# Power.net
KiCad netlist of a schematic drawn in Altium Designer
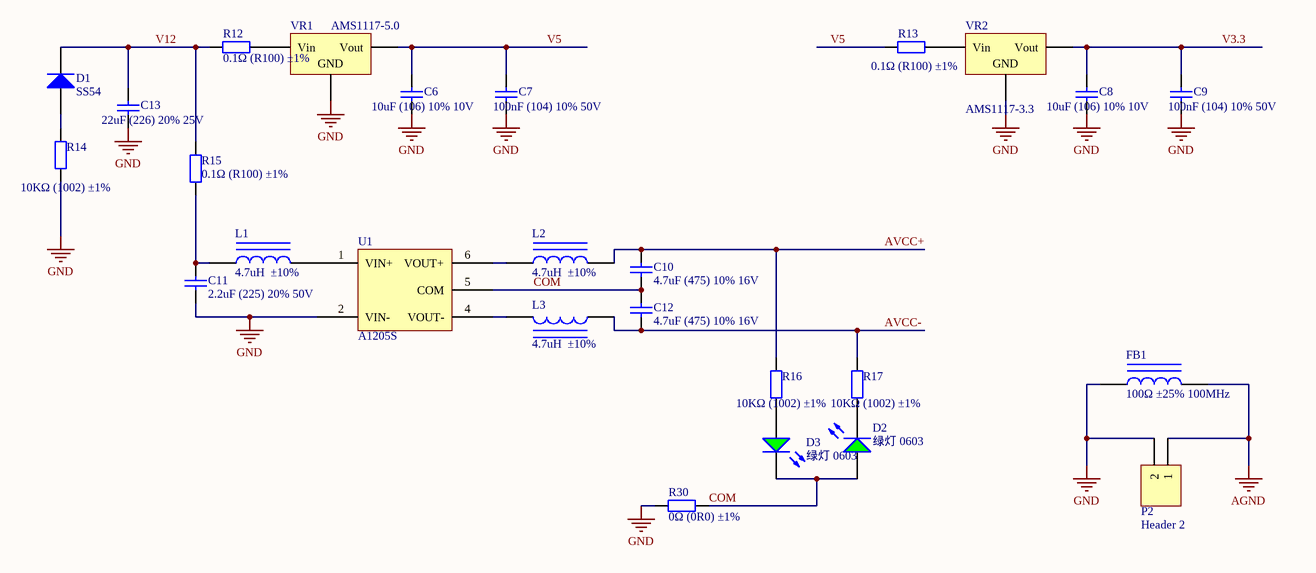
[diagram p0: Power.SchDoc]

(export (version "E")
  (design (tool "Eeschema 10.0.6"))
  (components
    (comp (ref "C6")
      (value "10uF (106) 10% 10V")
      (footprint "0603_C")
      (description "贴片电容")
      (libsource (lib "Miscellaneous Devices LC") (part "0603 10uF (106) 10% 10V"))
    )
    (comp (ref "C7")
      (value "100nF (104) 10% 50V")
      (footprint "0603_C")
      (description "贴片电容")
      (libsource (lib "Miscellaneous Devices LC") (part "0603 100nF (104) 10% 50V"))
    )
    (comp (ref "C8")
      (value "10uF (106) 10% 10V")
      (footprint "0603_C")
      (description "贴片电容")
      (libsource (lib "Miscellaneous Devices LC") (part "0603 10uF (106) 10% 10V"))
    )
    (comp (ref "C9")
      (value "100nF (104) 10% 50V")
      (footprint "0603_C")
      (description "贴片电容")
      (libsource (lib "Miscellaneous Devices LC") (part "0603 100nF (104) 10% 50V"))
    )
    (comp (ref "C10")
      (value "4.7uF (475) 10% 16V")
      (footprint "0603_C")
      (description "贴片电容")
      (libsource (lib "Miscellaneous Devices LC") (part "0603 4.7uF (475) 10% 16V"))
    )
    (comp (ref "C11")
      (value "2.2uF (225) 20% 50V")
      (footprint "0805_C")
      (description "贴片电容")
      (libsource (lib "Miscellaneous Devices LC") (part "0805 2.2uF (225) 20% 50V"))
    )
    (comp (ref "C12")
      (value "4.7uF (475) 10% 16V")
      (footprint "0603_C")
      (description "贴片电容")
      (libsource (lib "Miscellaneous Devices LC") (part "0603 4.7uF (475) 10% 16V"))
    )
    (comp (ref "C13")
      (value "22uF (226) 20% 25V")
      (footprint "0805_C")
      (description "贴片电容")
      (libsource (lib "Miscellaneous Devices LC") (part "0805 22uF (226) 20% 25V"))
    )
    (comp (ref "D1")
      (value "SS54")
      (footprint "SMA(DO-214AC)_S1")
      (description "二极管")
      (libsource (lib "Miscellaneous Devices LC") (part "SMA(DO-214AC) SS54"))
    )
    (comp (ref "D2")
      (value "绿灯 0603")
      (footprint "0603_LED_S1")
      (description "发光二极管")
      (libsource (lib "Miscellaneous Devices LC") (part "0603 绿灯"))
    )
    (comp (ref "D3")
      (value "绿灯 0603")
      (footprint "0603_LED_S1")
      (description "发光二极管")
      (libsource (lib "Miscellaneous Devices LC") (part "0603 绿灯"))
    )
    (comp (ref "FB1")
      (value "100Ω ±25% 100MHz")
      (footprint "0805_L")
      (description "贴片磁珠")
      (libsource (lib "Miscellaneous Devices LC") (part "0805 100Ω 25% 100MHz"))
    )
    (comp (ref "L1")
      (value "4.7uH  ±10%")
      (footprint "1206_L")
      (description "贴片电感")
      (libsource (lib "") (part "1206 4.7uH  10%_1"))
    )
    (comp (ref "L2")
      (value "4.7uH  ±10%")
      (footprint "1206_L")
      (description "贴片电感")
      (libsource (lib "") (part "1206 4.7uH  10%_1"))
    )
    (comp (ref "L3")
      (value "4.7uH  ±10%")
      (footprint "1206_L")
      (description "贴片电感")
      (libsource (lib "Miscellaneous Devices LC") (part "1206 4.7uH  10%"))
    )
    (comp (ref "P2")
      (value "Header 2")
      (footprint "HDR1X2")
      (description "Header, 2-Pin")
      (fields (field (name "PUBLISHER") "Altium Limited"))
      (libsource (lib "Miscellaneous Connectors") (part "Header 2"))
    )
    (comp (ref "R12")
      (value "0.1Ω (R100) ±1%")
      (footprint "1206_R")
      (description "贴片电阻")
      (libsource (lib "Miscellaneous Devices LC") (part "1206 0.1Ω (R100) 1%"))
    )
    (comp (ref "R13")
      (value "0.1Ω (R100) ±1%")
      (footprint "1206_R")
      (description "贴片电阻")
      (libsource (lib "Miscellaneous Devices LC") (part "1206 0.1Ω (R100) 1%"))
    )
    (comp (ref "R14")
      (value "10KΩ (1002) ±1%")
      (footprint "0805_R")
      (description "贴片电阻")
      (libsource (lib "Miscellaneous Devices LC") (part "0805 10KΩ (1002) 1%"))
    )
    (comp (ref "R15")
      (value "0.1Ω (R100) ±1%")
      (footprint "1206_R")
      (description "贴片电阻")
      (libsource (lib "") (part "1206 0.1Ω (R100) 1%_1"))
    )
    (comp (ref "R16")
      (value "10KΩ (1002) ±1%")
      (footprint "0603_R")
      (description "贴片电阻")
      (libsource (lib "Miscellaneous Devices LC") (part "0603 10KΩ (1002) 1%"))
    )
    (comp (ref "R17")
      (value "10KΩ (1002) ±1%")
      (footprint "0603_R")
      (description "贴片电阻")
      (libsource (lib "Miscellaneous Devices LC") (part "0603 10KΩ (1002) 1%"))
    )
    (comp (ref "R30")
      (value "0Ω (0R0) ±1%")
      (footprint "1206_R")
      (description "贴片电阻")
      (libsource (lib "Miscellaneous Devices LC") (part "1206 0Ω (0R0) 1%"))
    )
    (comp (ref "U1") (value "A1205S") (footprint "A1205S") (libsource (lib "CHK-I") (part "A1205S")))
    (comp (ref "VR1")
      (value "AMS1117-5.0")
      (footprint "SOT-223")
      (description "低压差线性稳压(LDO)")
      (libsource (lib "Miscellaneous Devices LC") (part "SOT-223 AMS1117-5.0"))
    )
    (comp (ref "VR2")
      (value "AMS1117-3.3")
      (footprint "SOT-223")
      (description "低压差线性稳压(LDO)")
      (libsource (lib "Miscellaneous Devices LC") (part "SOT-223 AMS1117-3.3"))
    )
  )
  (nets
    (net (code "1") (name "/AVCC+") (class "Default")
      (node (ref "C10") (pin "2") (pinfunction "2_2") (pintype "passive"))
      (node (ref "L2") (pin "2") (pinfunction "2_2") (pintype "passive"))
      (node (ref "R16") (pin "2") (pinfunction "2_2") (pintype "passive"))
    )
    (net (code "2") (name "/AVCC-") (class "Default")
      (node (ref "C12") (pin "1") (pinfunction "1_1") (pintype "passive"))
      (node (ref "L3") (pin "2") (pinfunction "2_2") (pintype "passive"))
      (node (ref "R17") (pin "2") (pinfunction "2_2") (pintype "passive"))
    )
    (net (code "3") (name "/COM") (class "Default")
      (node (ref "C10") (pin "1") (pinfunction "1_1") (pintype "passive"))
      (node (ref "C12") (pin "2") (pinfunction "2_2") (pintype "passive"))
      (node (ref "D2") (pin "A") (pinfunction "A_A") (pintype "passive"))
      (node (ref "D3") (pin "K") (pinfunction "K_K") (pintype "passive"))
      (node (ref "R30") (pin "2") (pinfunction "2_2") (pintype "passive"))
      (node (ref "U1") (pin "5") (pinfunction "COM_5") (pintype "passive"))
    )
    (net (code "4") (name "/V3.3") (class "Default")
      (node (ref "C8") (pin "2") (pinfunction "2_2") (pintype "passive"))
      (node (ref "C9") (pin "2") (pinfunction "2_2") (pintype "passive"))
      (node (ref "VR2") (pin "2") (pinfunction "Vout_2") (pintype "passive"))
    )
    (net (code "5") (name "/V5") (class "Default")
      (node (ref "C6") (pin "2") (pinfunction "2_2") (pintype "passive"))
      (node (ref "C7") (pin "2") (pinfunction "2_2") (pintype "passive"))
      (node (ref "R13") (pin "1") (pinfunction "1_1") (pintype "passive"))
      (node (ref "VR1") (pin "2") (pinfunction "Vout_2") (pintype "passive"))
    )
    (net (code "6") (name "/V12") (class "Default")
      (node (ref "C13") (pin "2") (pinfunction "2_2") (pintype "passive"))
      (node (ref "D1") (pin "2") (pinfunction "K_2") (pintype "passive"))
      (node (ref "R12") (pin "1") (pinfunction "1_1") (pintype "passive"))
      (node (ref "R15") (pin "2") (pinfunction "2_2") (pintype "passive"))
    )
    (net (code "7") (name "AGND") (class "Default")
      (node (ref "FB1") (pin "2") (pinfunction "2_2") (pintype "passive"))
      (node (ref "P2") (pin "1") (pinfunction "1_1") (pintype "passive"))
    )
    (net (code "8") (name "GND") (class "Default")
      (node (ref "C11") (pin "1") (pinfunction "1_1") (pintype "passive"))
      (node (ref "C13") (pin "1") (pinfunction "1_1") (pintype "passive"))
      (node (ref "C6") (pin "1") (pinfunction "1_1") (pintype "passive"))
      (node (ref "C7") (pin "1") (pinfunction "1_1") (pintype "passive"))
      (node (ref "C8") (pin "1") (pinfunction "1_1") (pintype "passive"))
      (node (ref "C9") (pin "1") (pinfunction "1_1") (pintype "passive"))
      (node (ref "FB1") (pin "1") (pinfunction "1_1") (pintype "passive"))
      (node (ref "P2") (pin "2") (pinfunction "2_2") (pintype "passive"))
      (node (ref "R14") (pin "1") (pinfunction "1_1") (pintype "passive"))
      (node (ref "R30") (pin "1") (pinfunction "1_1") (pintype "passive"))
      (node (ref "U1") (pin "2") (pinfunction "VIN-_2") (pintype "passive"))
      (node (ref "VR1") (pin "1") (pinfunction "GND_1") (pintype "passive"))
      (node (ref "VR2") (pin "1") (pinfunction "GND_1") (pintype "passive"))
    )
    (net (code "9") (name "Net-(C11-Pad2)") (class "Default")
      (node (ref "C11") (pin "2") (pinfunction "2_2") (pintype "passive"))
      (node (ref "L1") (pin "1") (pinfunction "1_1") (pintype "passive"))
      (node (ref "R15") (pin "1") (pinfunction "1_1") (pintype "passive"))
    )
    (net (code "10") (name "Net-(D1-A)") (class "Default")
      (node (ref "D1") (pin "1") (pinfunction "A_1") (pintype "passive"))
      (node (ref "R14") (pin "2") (pinfunction "2_2") (pintype "passive"))
    )
    (net (code "11") (name "Net-(D2-PadK)") (class "Default")
      (node (ref "D2") (pin "K") (pinfunction "K_K") (pintype "passive"))
      (node (ref "R17") (pin "1") (pinfunction "1_1") (pintype "passive"))
    )
    (net (code "12") (name "Net-(D3-PadA)") (class "Default")
      (node (ref "D3") (pin "A") (pinfunction "A_A") (pintype "passive"))
      (node (ref "R16") (pin "1") (pinfunction "1_1") (pintype "passive"))
    )
    (net (code "13") (name "Net-(U1-VIN+)") (class "Default")
      (node (ref "L1") (pin "2") (pinfunction "2_2") (pintype "passive"))
      (node (ref "U1") (pin "1") (pinfunction "VIN+_1") (pintype "passive"))
    )
    (net (code "14") (name "Net-(U1-VOUT+)") (class "Default")
      (node (ref "L2") (pin "1") (pinfunction "1_1") (pintype "passive"))
      (node (ref "U1") (pin "6") (pinfunction "VOUT+_6") (pintype "passive"))
    )
    (net (code "15") (name "Net-(U1-VOUT-)") (class "Default")
      (node (ref "L3") (pin "1") (pinfunction "1_1") (pintype "passive"))
      (node (ref "U1") (pin "4") (pinfunction "VOUT-_4") (pintype "passive"))
    )
    (net (code "16") (name "Net-(VR1-Vin)") (class "Default")
      (node (ref "R12") (pin "2") (pinfunction "2_2") (pintype "passive"))
      (node (ref "VR1") (pin "3") (pinfunction "Vin_3") (pintype "passive"))
    )
    (net (code "17") (name "Net-(VR2-Vin)") (class "Default")
      (node (ref "R13") (pin "2") (pinfunction "2_2") (pintype "passive"))
      (node (ref "VR2") (pin "3") (pinfunction "Vin_3") (pintype "passive"))
    )
  )
)
